# control_board.net
KiCad netlist of a schematic drawn in EAGLE
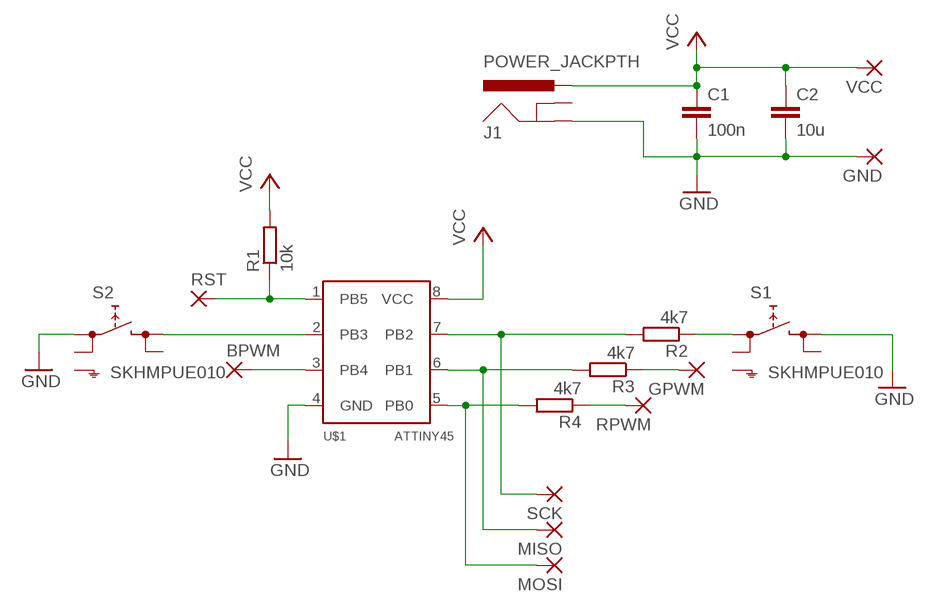
[diagram p0: schematic, sheet 1]

(export (version "E")
  (design (tool "Eeschema 10.0.6"))
  (components
    (comp (ref "BPWM")
      (value "SMD5")
      (footprint "eagle-import:SMD2,54-5,08")
      (libsource (lib "eagle-import") (part "SMD5"))
    )
    (comp (ref "C1")
      (value "100n")
      (footprint "eagle-import:C1206")
      (libsource (lib "eagle-import") (part "C-EUC1206"))
    )
    (comp (ref "C2")
      (value "10u")
      (footprint "eagle-import:C1206")
      (libsource (lib "eagle-import") (part "C-EUC1206"))
    )
    (comp (ref "GND")
      (value "SMD5")
      (footprint "eagle-import:SMD2,54-5,08")
      (libsource (lib "eagle-import") (part "SMD5"))
    )
    (comp (ref "GPWM")
      (value "SMD5")
      (footprint "eagle-import:SMD2,54-5,08")
      (libsource (lib "eagle-import") (part "SMD5"))
    )
    (comp (ref "J1")
      (value "POWER_JACKPTH")
      (footprint "eagle-import:POWER_JACK_PTH")
      (libsource (lib "eagle-import") (part "POWER_JACKPTH"))
    )
    (comp (ref "MISO")
      (value "SMD2")
      (footprint "eagle-import:SMD1,27-2,54")
      (libsource (lib "eagle-import") (part "SMD2"))
    )
    (comp (ref "MOSI")
      (value "SMD2")
      (footprint "eagle-import:SMD1,27-2,54")
      (libsource (lib "eagle-import") (part "SMD2"))
    )
    (comp (ref "R1")
      (value "10k")
      (footprint "eagle-import:R1206")
      (libsource (lib "eagle-import") (part "R-EU_R1206"))
    )
    (comp (ref "R2")
      (value "4k7")
      (footprint "eagle-import:R1206")
      (libsource (lib "eagle-import") (part "R-EU_R1206"))
    )
    (comp (ref "R3")
      (value "4k7")
      (footprint "eagle-import:R1206")
      (libsource (lib "eagle-import") (part "R-EU_R1206"))
    )
    (comp (ref "R4")
      (value "4k7")
      (footprint "eagle-import:R1206")
      (libsource (lib "eagle-import") (part "R-EU_R1206"))
    )
    (comp (ref "RPWM")
      (value "SMD5")
      (footprint "eagle-import:SMD2,54-5,08")
      (libsource (lib "eagle-import") (part "SMD5"))
    )
    (comp (ref "RST")
      (value "SMD2")
      (footprint "eagle-import:SMD1,27-2,54")
      (libsource (lib "eagle-import") (part "SMD2"))
    )
    (comp (ref "S1")
      (value "SKHMPUE010")
      (footprint "eagle-import:SKHMPXE010")
      (libsource (lib "eagle-import") (part "SKHMPE010U"))
    )
    (comp (ref "S2")
      (value "SKHMPUE010")
      (footprint "eagle-import:SKHMPXE010")
      (libsource (lib "eagle-import") (part "SKHMPE010U"))
    )
    (comp (ref "SCK")
      (value "SMD2")
      (footprint "eagle-import:SMD1,27-2,54")
      (libsource (lib "eagle-import") (part "SMD2"))
    )
    (comp (ref "U$1")
      (value "ATTINY45")
      (footprint "eagle-import:SOIC8")
      (libsource (lib "eagle-import") (part "ATTINY45"))
    )
    (comp (ref "VCC")
      (value "SMD5")
      (footprint "eagle-import:SMD2,54-5,08")
      (libsource (lib "eagle-import") (part "SMD5"))
    )
  )
  (nets
    (net (code "1") (name "GND") (class "Default")
      (node (ref "C1") (pin "2") (pinfunction "2_2") (pintype "passive"))
      (node (ref "C2") (pin "2") (pinfunction "2_2") (pintype "passive"))
      (node (ref "GND") (pin "1") (pinfunction "P_1") (pintype "passive"))
      (node (ref "J1") (pin "GND") (pinfunction "GND_GND") (pintype "bidirectional"))
      (node (ref "S1") (pin "3") (pinfunction "2.1_3") (pintype "passive"))
      (node (ref "S2") (pin "1") (pinfunction "1.1_1") (pintype "passive"))
      (node (ref "U$1") (pin "4") (pinfunction "GND_4") (pintype "power_in"))
    )
    (net (code "2") (name "Net-(BPWM-P)") (class "Default")
      (node (ref "BPWM") (pin "1") (pinfunction "P_1") (pintype "passive"))
      (node (ref "U$1") (pin "3") (pinfunction "PB4_3") (pintype "bidirectional"))
    )
    (net (code "3") (name "Net-(GPWM-P)") (class "Default")
      (node (ref "GPWM") (pin "1") (pinfunction "P_1") (pintype "passive"))
      (node (ref "R3") (pin "1") (pinfunction "1_1") (pintype "passive"))
    )
    (net (code "4") (name "Net-(MISO-P)") (class "Default")
      (node (ref "MISO") (pin "1") (pinfunction "P_1") (pintype "passive"))
      (node (ref "R3") (pin "2") (pinfunction "2_2") (pintype "passive"))
      (node (ref "U$1") (pin "6") (pinfunction "PB1_6") (pintype "bidirectional"))
    )
    (net (code "5") (name "Net-(MOSI-P)") (class "Default")
      (node (ref "MOSI") (pin "1") (pinfunction "P_1") (pintype "passive"))
      (node (ref "R4") (pin "2") (pinfunction "2_2") (pintype "passive"))
      (node (ref "U$1") (pin "5") (pinfunction "PB0_5") (pintype "bidirectional"))
    )
    (net (code "6") (name "Net-(RPWM-P)") (class "Default")
      (node (ref "R4") (pin "1") (pinfunction "1_1") (pintype "passive"))
      (node (ref "RPWM") (pin "1") (pinfunction "P_1") (pintype "passive"))
    )
    (net (code "7") (name "Net-(RST-P)") (class "Default")
      (node (ref "R1") (pin "1") (pinfunction "1_1") (pintype "passive"))
      (node (ref "RST") (pin "1") (pinfunction "P_1") (pintype "passive"))
      (node (ref "U$1") (pin "1") (pinfunction "PB5_1") (pintype "bidirectional"))
    )
    (net (code "8") (name "Net-(S1-1.1)") (class "Default")
      (node (ref "R2") (pin "1") (pinfunction "1_1") (pintype "passive"))
      (node (ref "S1") (pin "1") (pinfunction "1.1_1") (pintype "passive"))
    )
    (net (code "9") (name "Net-(S2-2.1)") (class "Default")
      (node (ref "S2") (pin "3") (pinfunction "2.1_3") (pintype "passive"))
      (node (ref "U$1") (pin "2") (pinfunction "PB3_2") (pintype "bidirectional"))
    )
    (net (code "10") (name "Net-(SCK-P)") (class "Default")
      (node (ref "R2") (pin "2") (pinfunction "2_2") (pintype "passive"))
      (node (ref "SCK") (pin "1") (pinfunction "P_1") (pintype "passive"))
      (node (ref "U$1") (pin "7") (pinfunction "PB2_7") (pintype "bidirectional"))
    )
    (net (code "11") (name "VCC") (class "Default")
      (node (ref "C1") (pin "1") (pinfunction "1_1") (pintype "passive"))
      (node (ref "C2") (pin "1") (pinfunction "1_1") (pintype "passive"))
      (node (ref "J1") (pin "PWR") (pinfunction "PWR_PWR") (pintype "bidirectional"))
      (node (ref "R1") (pin "2") (pinfunction "2_2") (pintype "passive"))
      (node (ref "U$1") (pin "8") (pinfunction "VCC_8") (pintype "power_in"))
      (node (ref "VCC") (pin "1") (pinfunction "P_1") (pintype "passive"))
    )
    (net (code "12") (name "unconnected-(J1-PadGNDBREAK)") (class "Default")
      (node (ref "J1") (pin "GNDBREAK") (pinfunction "GNDBREAK_GNDBREAK") (pintype "bidirectional"))
    )
    (net (code "13") (name "unconnected-(S1-1.2-Pad2)") (class "Default")
      (node (ref "S1") (pin "2") (pinfunction "1.2_2") (pintype "passive"))
    )
    (net (code "14") (name "unconnected-(S1-2.2-Pad4)") (class "Default")
      (node (ref "S1") (pin "4") (pinfunction "2.2_4") (pintype "passive"))
    )
    (net (code "15") (name "unconnected-(S1-SH-Pad5)") (class "Default")
      (node (ref "S1") (pin "5") (pinfunction "SH_5") (pintype "passive"))
    )
    (net (code "16") (name "unconnected-(S2-1.2-Pad2)") (class "Default")
      (node (ref "S2") (pin "2") (pinfunction "1.2_2") (pintype "passive"))
    )
    (net (code "17") (name "unconnected-(S2-2.2-Pad4)") (class "Default")
      (node (ref "S2") (pin "4") (pinfunction "2.2_4") (pintype "passive"))
    )
    (net (code "18") (name "unconnected-(S2-SH-Pad5)") (class "Default")
      (node (ref "S2") (pin "5") (pinfunction "SH_5") (pintype "passive"))
    )
  )
)
